# MCU.net
KiCad netlist of a schematic drawn in Altium Designer
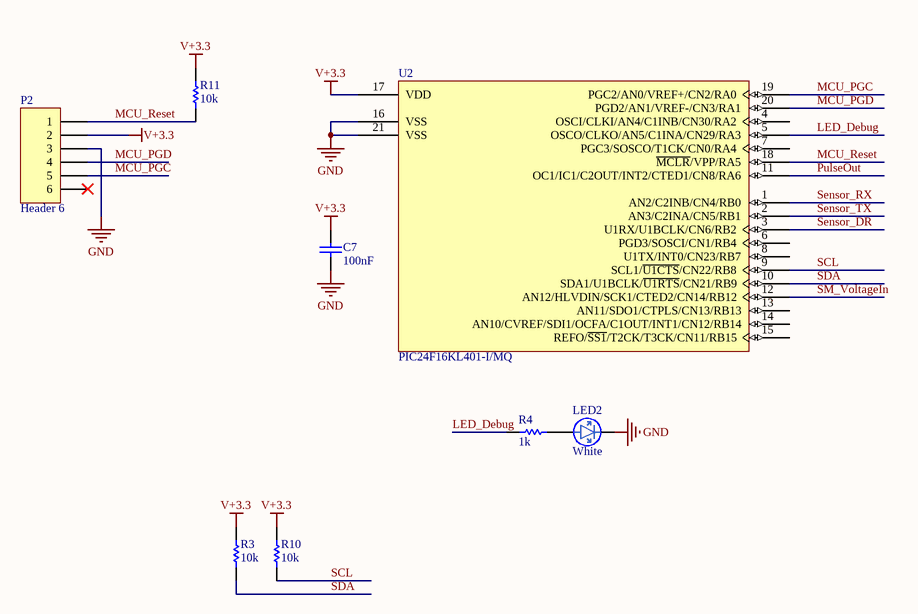
[diagram p0: MCU.SchDoc]

(export (version "E")
  (design (tool "Eeschema 10.0.6"))
  (components
    (comp (ref "C7")
      (value "100nF")
      (footprint "0603")
      (description "Capacitor (Semiconductor SIM Model)")
      (fields (field (name "PUBLISHER") "Altium Limited"))
      (libsource (lib "Miscellaneous Devices") (part "Cap Semi"))
    )
    (comp (ref "LED2")
      (value "White")
      (footprint "LED-0603-RED")
      (libsource (lib "Library_Schematic") (part "SMD_LED_0805"))
    )
    (comp (ref "P2")
      (value "Header 6")
      (footprint "MHDR1X6")
      (description "Header, 6-Pin")
      (fields (field (name "PUBLISHER") "Altium Limited"))
      (libsource (lib "Miscellaneous Connectors") (part "Header 6"))
    )
    (comp (ref "R3")
      (value "10k")
      (footprint "0603")
      (description "Resistor")
      (fields (field (name "PUBLISHER") "Altium Limited"))
      (libsource (lib "Miscellaneous Devices") (part "Res1"))
    )
    (comp (ref "R4")
      (value "1k")
      (footprint "0603")
      (description "Resistor")
      (fields (field (name "PUBLISHER") "Altium Limited"))
      (libsource (lib "Miscellaneous Devices") (part "Res1"))
    )
    (comp (ref "R10")
      (value "10k")
      (footprint "0603")
      (description "Resistor")
      (fields (field (name "PUBLISHER") "Altium Limited"))
      (libsource (lib "Miscellaneous Devices") (part "Res1"))
    )
    (comp (ref "R11")
      (value "10k")
      (footprint "0603")
      (description "Resistor")
      (fields (field (name "PUBLISHER") "Altium Limited"))
      (libsource (lib "Miscellaneous Devices") (part "Res1"))
    )
    (comp (ref "U2")
      (value "PIC24F16KL401-I/MQ")
      (footprint "QFN-MQ20_N")
      (fields (field (name "PUBLISHER") "Altium Limited"))
      (libsource (lib "Microchip Microcontroller 16-Bit PIC24F") (part "PIC24F04KA201T-I/MQ"))
    )
  )
  (nets
    (net (code "1") (name "/LED_Debug") (class "Default")
      (node (ref "R4") (pin "1") (pinfunction "1_1") (pintype "passive"))
      (node (ref "U2") (pin "5") (pinfunction "OSCO/CLKO/AN5/C1INA/CN29/RA3_5") (pintype "bidirectional"))
    )
    (net (code "2") (name "/MCU_PGC") (class "Default")
      (node (ref "P2") (pin "5") (pinfunction "5_5") (pintype "passive"))
      (node (ref "U2") (pin "19") (pinfunction "PGC2/AN0/VREF+/CN2/RA0_19") (pintype "bidirectional"))
    )
    (net (code "3") (name "/MCU_PGD") (class "Default")
      (node (ref "P2") (pin "4") (pinfunction "4_4") (pintype "passive"))
      (node (ref "U2") (pin "20") (pinfunction "PGD2/AN1/VREF-/CN3/RA1_20") (pintype "bidirectional"))
    )
    (net (code "4") (name "/MCU_Reset") (class "Default")
      (node (ref "P2") (pin "1") (pinfunction "1_1") (pintype "passive"))
      (node (ref "R11") (pin "1") (pinfunction "1_1") (pintype "passive"))
      (node (ref "U2") (pin "18") (pinfunction "~{MCLR}/VPP/RA5_18") (pintype "bidirectional"))
    )
    (net (code "5") (name "/PulseOut") (class "Default")
      (node (ref "U2") (pin "11") (pinfunction "OC1/IC1/C2OUT/INT2/CTED1/CN8/RA6_11") (pintype "bidirectional"))
    )
    (net (code "6") (name "/SCL") (class "Default")
      (node (ref "R10") (pin "1") (pinfunction "1_1") (pintype "passive"))
      (node (ref "U2") (pin "9") (pinfunction "SCL1/~{U1CTS}/CN22/RB8_9") (pintype "bidirectional"))
    )
    (net (code "7") (name "/SDA") (class "Default")
      (node (ref "R3") (pin "1") (pinfunction "1_1") (pintype "passive"))
      (node (ref "U2") (pin "10") (pinfunction "SDA1/U1BCLK/~{U1RTS}/CN21/RB9_10") (pintype "bidirectional"))
    )
    (net (code "8") (name "/SM_VoltageIn") (class "Default")
      (node (ref "U2") (pin "12") (pinfunction "AN12/HLVDIN/SCK1/CTED2/CN14/RB12_12") (pintype "bidirectional"))
    )
    (net (code "9") (name "/Sensor_DR") (class "Default")
      (node (ref "U2") (pin "3") (pinfunction "U1RX/U1BCLK/CN6/RB2_3") (pintype "bidirectional"))
    )
    (net (code "10") (name "/Sensor_RX") (class "Default")
      (node (ref "U2") (pin "1") (pinfunction "AN2/C2INB/CN4/RB0_1") (pintype "bidirectional"))
    )
    (net (code "11") (name "/Sensor_TX") (class "Default")
      (node (ref "U2") (pin "2") (pinfunction "AN3/C2INA/CN5/RB1_2") (pintype "bidirectional"))
    )
    (net (code "12") (name "GND") (class "Default")
      (node (ref "C7") (pin "2") (pinfunction "2_2") (pintype "passive"))
      (node (ref "LED2") (pin "K") (pintype "passive"))
      (node (ref "P2") (pin "3") (pinfunction "3_3") (pintype "passive"))
      (node (ref "U2") (pin "16") (pinfunction "VSS_16") (pintype "power_in"))
      (node (ref "U2") (pin "21") (pinfunction "VSS_21") (pintype "power_in"))
    )
    (net (code "13") (name "Net-(LED2-PadA)") (class "Default")
      (node (ref "LED2") (pin "A") (pintype "passive"))
      (node (ref "R4") (pin "2") (pinfunction "2_2") (pintype "passive"))
    )
    (net (code "14") (name "V+3.3") (class "Default")
      (node (ref "C7") (pin "1") (pinfunction "1_1") (pintype "passive"))
      (node (ref "P2") (pin "2") (pinfunction "2_2") (pintype "passive"))
      (node (ref "R10") (pin "2") (pinfunction "2_2") (pintype "passive"))
      (node (ref "R11") (pin "2") (pinfunction "2_2") (pintype "passive"))
      (node (ref "R3") (pin "2") (pinfunction "2_2") (pintype "passive"))
      (node (ref "U2") (pin "17") (pinfunction "VDD_17") (pintype "power_in"))
    )
    (net (code "15") (name "unconnected-(P2-Pad6)") (class "Default")
      (node (ref "P2") (pin "6") (pinfunction "6_6") (pintype "passive+no_connect"))
    )
    (net (code "16") (name "unconnected-(U2-AN10{slash}CVREF{slash}SDI1{slash}OCFA{slash}C1OUT{slash}INT1{slash}CN12{slash}RB14-Pad14)") (class "Default")
      (node (ref "U2") (pin "14") (pinfunction "AN10/CVREF/SDI1/OCFA/C1OUT/INT1/CN12/RB14_14") (pintype "bidirectional"))
    )
    (net (code "17") (name "unconnected-(U2-AN11{slash}SDO1{slash}CTPLS{slash}CN13{slash}RB13-Pad13)") (class "Default")
      (node (ref "U2") (pin "13") (pinfunction "AN11/SDO1/CTPLS/CN13/RB13_13") (pintype "bidirectional"))
    )
    (net (code "18") (name "unconnected-(U2-OSCI{slash}CLKI{slash}AN4{slash}C1INB{slash}CN30{slash}RA2-Pad4)") (class "Default")
      (node (ref "U2") (pin "4") (pinfunction "OSCI/CLKI/AN4/C1INB/CN30/RA2_4") (pintype "bidirectional"))
    )
    (net (code "19") (name "unconnected-(U2-PGC3{slash}SOSCO{slash}T1CK{slash}CN0{slash}RA4-Pad7)") (class "Default")
      (node (ref "U2") (pin "7") (pinfunction "PGC3/SOSCO/T1CK/CN0/RA4_7") (pintype "bidirectional"))
    )
    (net (code "20") (name "unconnected-(U2-PGD3{slash}SOSCI{slash}CN1{slash}RB4-Pad6)") (class "Default")
      (node (ref "U2") (pin "6") (pinfunction "PGD3/SOSCI/CN1/RB4_6") (pintype "bidirectional"))
    )
    (net (code "21") (name "unconnected-(U2-REFO{slash}~{SS1}{slash}T2CK{slash}T3CK{slash}CN11{slash}RB15-Pad15)") (class "Default")
      (node (ref "U2") (pin "15") (pinfunction "REFO/~{SS1}/T2CK/T3CK/CN11/RB15_15") (pintype "bidirectional"))
    )
    (net (code "22") (name "unconnected-(U2-U1TX{slash}INT0{slash}CN23{slash}RB7-Pad8)") (class "Default")
      (node (ref "U2") (pin "8") (pinfunction "U1TX/INT0/CN23/RB7_8") (pintype "bidirectional"))
    )
  )
)
